# FPGA_I2C.net
KiCad netlist of a schematic drawn in Altium Designer
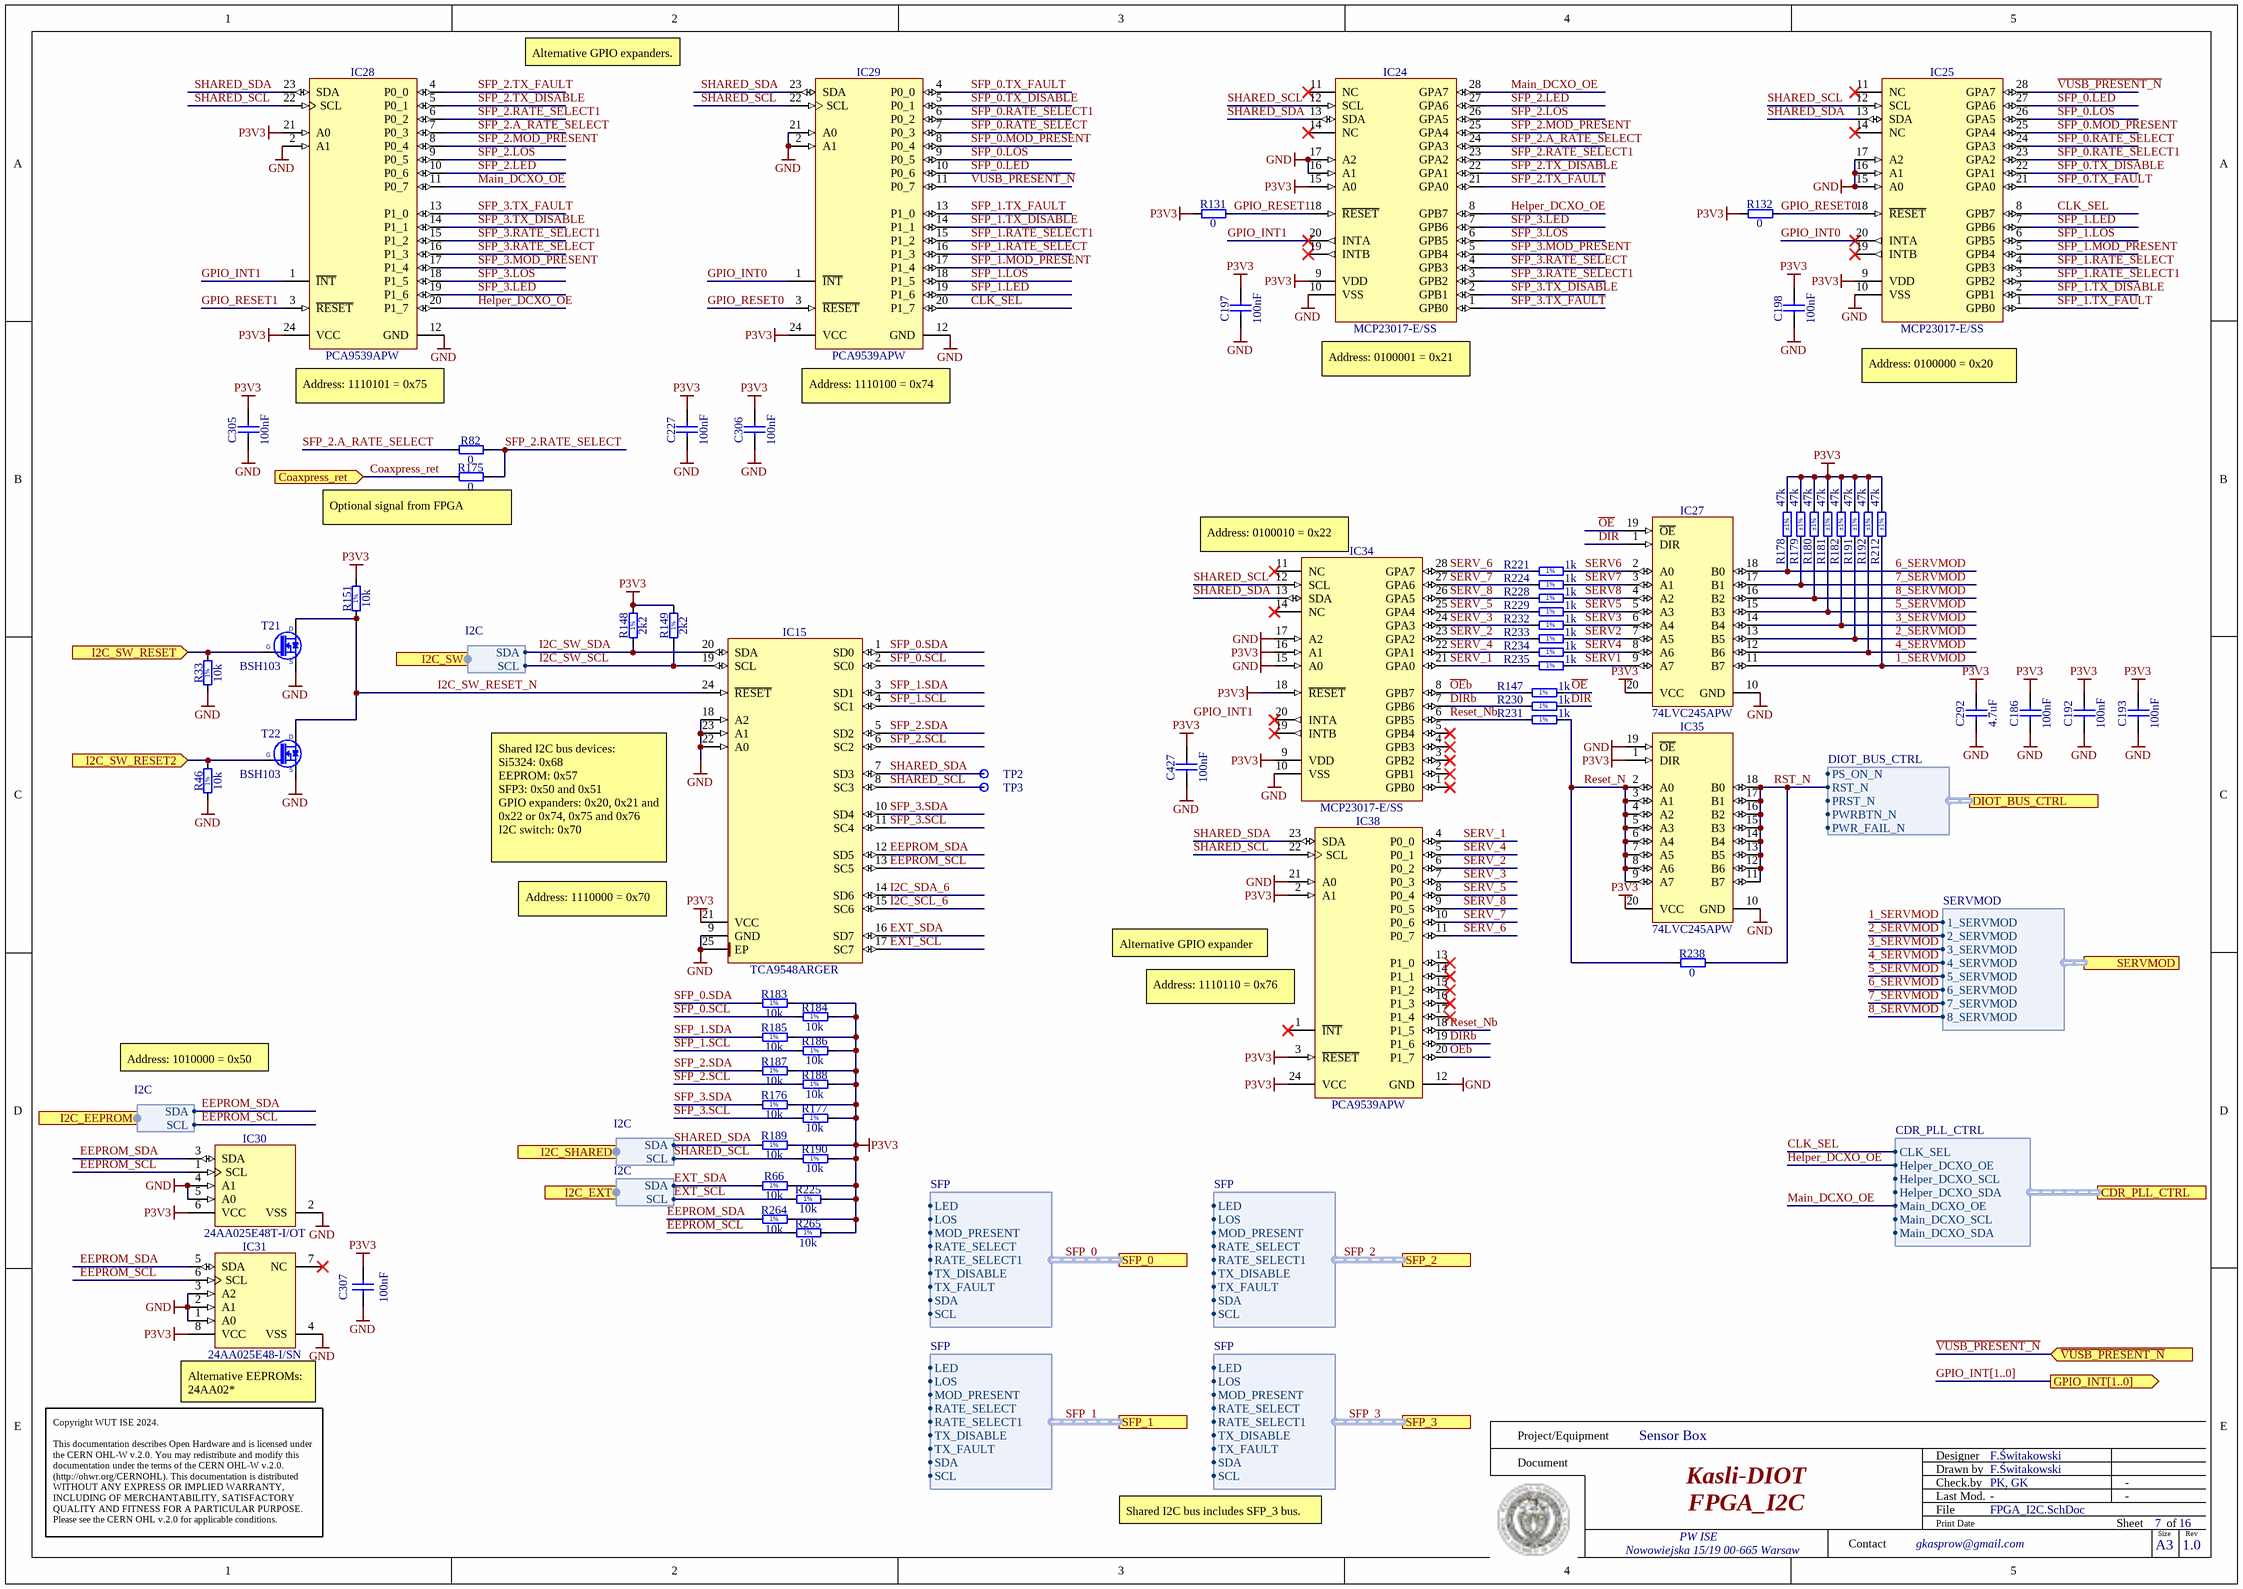
[diagram p0: FPGA_I2C.SchDoc]

(export (version "E")
  (design (tool "Eeschema 10.0.6"))
  (components
    (comp (ref "C186")
      (value "100nF")
      (footprint "CAPC1005X55N")
      (description "Non-polarised capacitor")
      (fields (field (name "PART NUMBER") "CC0402_100NF_16V_10%_X7R") (field (name "VOLTAGE") "16V"))
      (libsource (lib "Capacitors") (part "Capacitor - non polarized"))
    )
    (comp (ref "C192")
      (value "100nF")
      (footprint "CAPC1005X55N")
      (description "Non-polarised capacitor")
      (fields (field (name "PART NUMBER") "CC0402_100NF_16V_10%_X7R") (field (name "VOLTAGE") "16V"))
      (libsource (lib "Capacitors") (part "Capacitor - non polarized"))
    )
    (comp (ref "C193")
      (value "100nF")
      (footprint "CAPC1005X55N")
      (description "Non-polarised capacitor")
      (fields (field (name "PART NUMBER") "CC0402_100NF_16V_10%_X7R") (field (name "VOLTAGE") "16V"))
      (libsource (lib "Capacitors") (part "Capacitor - non polarized"))
    )
    (comp (ref "C197")
      (value "100nF")
      (footprint "CAPC1005X55N")
      (description "Non-polarised capacitor")
      (fields (field (name "PART NUMBER") "CC0402_100NF_16V_10%_X7R") (field (name "VOLTAGE") "16V"))
      (libsource (lib "Capacitors") (part "Capacitor - non polarized"))
    )
    (comp (ref "C198")
      (value "100nF")
      (footprint "CAPC1005X55N")
      (description "Non-polarised capacitor")
      (fields (field (name "PART NUMBER") "CC0402_100NF_16V_10%_X7R") (field (name "VOLTAGE") "16V"))
      (libsource (lib "Capacitors") (part "Capacitor - non polarized"))
    )
    (comp (ref "C227")
      (value "100nF")
      (footprint "CAPC1005X55N")
      (description "Non-polarised capacitor")
      (fields (field (name "PART NUMBER") "CC0402_100NF_16V_10%_X7R") (field (name "VOLTAGE") "16V"))
      (libsource (lib "Capacitors") (part "Capacitor - non polarized"))
    )
    (comp (ref "C292")
      (value "4.7uF")
      (footprint "CAPC1005X55N")
      (description "Non-polarised capacitor")
      (fields (field (name "PART NUMBER") "CC0402_4.7UF_6.3V_20%_X5R") (field (name "VOLTAGE") "6.3V"))
      (libsource (lib "Capacitors") (part "Capacitor - non polarized"))
    )
    (comp (ref "C305")
      (value "100nF")
      (footprint "CAPC1005X55N")
      (description "Non-polarised capacitor")
      (fields (field (name "PART NUMBER") "CC0402_100NF_16V_10%_X7R") (field (name "VOLTAGE") "16V"))
      (libsource (lib "Capacitors") (part "Capacitor - non polarized"))
    )
    (comp (ref "C306")
      (value "100nF")
      (footprint "CAPC1005X55N")
      (description "Non-polarised capacitor")
      (fields (field (name "PART NUMBER") "CC0402_100NF_16V_10%_X7R") (field (name "VOLTAGE") "16V"))
      (libsource (lib "Capacitors") (part "Capacitor - non polarized"))
    )
    (comp (ref "C307")
      (value "100nF")
      (footprint "CAPC1005X55N")
      (description "Non-polarised capacitor")
      (fields (field (name "PART NUMBER") "CC0402_100NF_16V_10%_X5R") (field (name "VOLTAGE") "16V"))
      (libsource (lib "Capacitors") (part "Capacitor - non polarized"))
    )
    (comp (ref "C427")
      (value "100nF")
      (footprint "CAPC1005X55N")
      (description "Non-polarised capacitor")
      (fields (field (name "PART NUMBER") "CC0402_100NF_16V_10%_X7R") (field (name "VOLTAGE") "16V"))
      (libsource (lib "Capacitors") (part "Capacitor - non polarized"))
    )
    (comp (ref "IC15")
      (value "TCA9548ARGER")
      (footprint "QFN50P400X400X100-25N-S220")
      (description "Low Voltage 8-Channel I2C Switch With Reset")
      (fields (field (name "MANUFACTURER") "TEXAS INSTRUMENTS"))
      (libsource (lib "ICs And Semiconductors") (part "TCA9548ARGER"))
    )
    (comp (ref "IC24")
      (value "MCP23017-E/SS")
      (footprint "SOP65P780X200-28N")
      (description "16-bit I/O Port Expander With Serial Interface")
      (fields (field (name "MANUFACTURER") "MICROCHIP TECHNOLOGY"))
      (libsource (lib "ICs And Semiconductors") (part "MCP23017-E/SS"))
    )
    (comp (ref "IC25")
      (value "MCP23017-E/SS")
      (footprint "SOP65P780X200-28N")
      (description "16-bit I/O Port Expander With Serial Interface")
      (fields (field (name "MANUFACTURER") "MICROCHIP TECHNOLOGY"))
      (libsource (lib "ICs And Semiconductors") (part "MCP23017-E/SS"))
    )
    (comp (ref "IC27")
      (value "74LVC245APW")
      (footprint "SOP65P640X110-20N")
      (description "Octal Bi-Directional Transceiver with 3-State Inputs/Outputs")
      (fields (field (name "MANUFACTURER") "NXP SEMICONDUCTORS"))
      (libsource (lib "ICs And Semiconductors") (part "74245"))
    )
    (comp (ref "IC28")
      (value "PCA9539APW")
      (footprint "SOP65P640X110-24N")
      (description "Low-Voltage 16-Bit I2C-Bus I/O Port with Interrupt and Reset")
      (fields (field (name "MANUFACTURER") "NXP SEMICONDUCTORS"))
      (libsource (lib "ICs And Semiconductors") (part "PCA9539APW"))
    )
    (comp (ref "IC29")
      (value "PCA9539APW")
      (footprint "SOP65P640X110-24N")
      (description "Low-Voltage 16-Bit I2C-Bus I/O Port with Interrupt and Reset")
      (fields (field (name "MANUFACTURER") "NXP SEMICONDUCTORS"))
      (libsource (lib "ICs And Semiconductors") (part "PCA9539APW"))
    )
    (comp (ref "IC30")
      (value "24AA025E48T-I/OT")
      (footprint "SOT95P280X145-6N")
      (description "1.7V-5.5V, 2K I2C Serial EEPROM With EUI-48 Node Identity")
      (fields (field (name "MANUFACTURER") "MICROCHIP TECHNOLOGY"))
      (libsource (lib "ICs And Semiconductors") (part "24AA025E48T-I/OT"))
    )
    (comp (ref "IC31")
      (value "24AA025E48-I/SN")
      (footprint "SOIC127P600X175-8N")
      (description "1.7V-5.5V, 2K I2C™ Serial EEPROMs with EUI-48™ Node Identity")
      (fields (field (name "MANUFACTURER") "MICROCHIP TECHNOLOGY"))
      (libsource (lib "ICs And Semiconductors") (part "24AA025E48-I/SN"))
    )
    (comp (ref "IC34")
      (value "MCP23017-E/SS")
      (footprint "SOP65P780X200-28N")
      (description "16-bit I/O Port Expander With Serial Interface")
      (fields (field (name "MANUFACTURER") "MICROCHIP TECHNOLOGY"))
      (libsource (lib "ICs And Semiconductors") (part "MCP23017-E/SS"))
    )
    (comp (ref "IC35")
      (value "74LVC245APW")
      (footprint "SOP65P640X110-20N")
      (description "Octal Bi-Directional Transceiver with 3-State Inputs/Outputs")
      (fields (field (name "MANUFACTURER") "NXP SEMICONDUCTORS"))
      (libsource (lib "ICs And Semiconductors") (part "74245"))
    )
    (comp (ref "IC38")
      (value "PCA9539APW")
      (footprint "SOP65P640X110-24N")
      (description "Low-Voltage 16-Bit I2C-Bus I/O Port with Interrupt and Reset")
      (fields (field (name "MANUFACTURER") "NXP SEMICONDUCTORS"))
      (libsource (lib "ICs And Semiconductors") (part "PCA9539APW"))
    )
    (comp (ref "R33")
      (value "10k")
      (footprint "RESC1005X40N")
      (description "Resistor - 1%")
      (fields (field (name "PART NUMBER") "R0402_10K_1%_0.0625W_100PPM") (field (name "POWER") "0.0625W"))
      (libsource (lib "Resistors") (part "Resistor - 1%"))
    )
    (comp (ref "R46")
      (value "10k")
      (footprint "RESC1005X40N")
      (description "Resistor - 1%")
      (fields (field (name "PART NUMBER") "R0402_10K_1%_0.0625W_100PPM") (field (name "POWER") "0.0625W"))
      (libsource (lib "Resistors") (part "Resistor - 1%"))
    )
    (comp (ref "R66")
      (value "10k")
      (footprint "RESC1005X40N")
      (description "Resistor - 1%")
      (fields (field (name "PART NUMBER") "R0402_10K_1%_0.0625W_100PPM") (field (name "POWER") "0.0625W"))
      (libsource (lib "Resistors") (part "Resistor - 1%"))
    )
    (comp (ref "R82")
      (value "0")
      (footprint "RESC1005X40N")
      (description "Resistor")
      (fields (field (name "PART NUMBER") "R0402_0R_JUMPER") (field (name "MANUFACTURER") "GENERIC"))
      (libsource (lib "Resistors") (part "Resistor"))
    )
    (comp (ref "R131")
      (value "0")
      (footprint "RESC1005X40N")
      (description "Resistor")
      (fields (field (name "PART NUMBER") "R0402_0R_JUMPER") (field (name "MANUFACTURER") "GENERIC"))
      (libsource (lib "Resistors") (part "Resistor"))
    )
    (comp (ref "R132")
      (value "0")
      (footprint "RESC1005X40N")
      (description "Resistor")
      (fields (field (name "PART NUMBER") "R0402_0R_JUMPER") (field (name "MANUFACTURER") "GENERIC"))
      (libsource (lib "Resistors") (part "Resistor"))
    )
    (comp (ref "R147")
      (value "1k")
      (footprint "RESC1005X40N")
      (description "Resistor - 1%")
      (fields (field (name "PART NUMBER") "R0402_1K_1%_0.0625W_100PPM") (field (name "POWER") "0.0625W"))
      (libsource (lib "Resistors") (part "Resistor - 1%"))
    )
    (comp (ref "R148")
      (value "2k2")
      (footprint "RESC1005X40N")
      (description "Resistor - 1%")
      (fields (field (name "PART NUMBER") "R0402_2K2_1%_0.0625W_100PPM") (field (name "POWER") "0.0625W"))
      (libsource (lib "Resistors") (part "Resistor - 1%"))
    )
    (comp (ref "R149")
      (value "2k2")
      (footprint "RESC1005X40N")
      (description "Resistor - 1%")
      (fields (field (name "PART NUMBER") "R0402_2K2_1%_0.0625W_100PPM") (field (name "POWER") "0.0625W"))
      (libsource (lib "Resistors") (part "Resistor - 1%"))
    )
    (comp (ref "R151")
      (value "10k")
      (footprint "RESC1005X40N")
      (description "Resistor - 1%")
      (fields (field (name "PART NUMBER") "R0402_10K_1%_0.0625W_100PPM") (field (name "POWER") "0.0625W"))
      (libsource (lib "Resistors") (part "Resistor - 1%"))
    )
    (comp (ref "R175")
      (value "0")
      (footprint "RESC1005X40N")
      (description "Resistor")
      (fields (field (name "PART NUMBER") "R0402_0R_JUMPER") (field (name "MANUFACTURER") "GENERIC"))
      (libsource (lib "Resistors") (part "Resistor"))
    )
    (comp (ref "R176")
      (value "10k")
      (footprint "RESC1005X40N")
      (description "Resistor - 1%")
      (fields (field (name "PART NUMBER") "R0402_10K_1%_0.0625W_100PPM") (field (name "POWER") "0.0625W"))
      (libsource (lib "Resistors") (part "Resistor - 1%"))
    )
    (comp (ref "R177")
      (value "10k")
      (footprint "RESC1005X40N")
      (description "Resistor - 1%")
      (fields (field (name "PART NUMBER") "R0402_10K_1%_0.0625W_100PPM") (field (name "POWER") "0.0625W"))
      (libsource (lib "Resistors") (part "Resistor - 1%"))
    )
    (comp (ref "R178")
      (value "47k")
      (footprint "RESC1005X40N")
      (description "Resistor - 1%")
      (fields
        (field (name "TOLERANCE") "±1%")
        (field (name "PART NUMBER") "R0402_47K_1%_0.0625W_100PPM")
        (field (name "POWER") "0.0625W")
      )
      (libsource (lib "Resistors") (part "Resistor - 1%"))
    )
    (comp (ref "R179")
      (value "47k")
      (footprint "RESC1005X40N")
      (description "Resistor - 1%")
      (fields
        (field (name "TOLERANCE") "±1%")
        (field (name "PART NUMBER") "R0402_47K_1%_0.0625W_100PPM")
        (field (name "POWER") "0.0625W")
      )
      (libsource (lib "Resistors") (part "Resistor - 1%"))
    )
    (comp (ref "R180")
      (value "47k")
      (footprint "RESC1005X40N")
      (description "Resistor - 1%")
      (fields
        (field (name "TOLERANCE") "±1%")
        (field (name "PART NUMBER") "R0402_47K_1%_0.0625W_100PPM")
        (field (name "POWER") "0.0625W")
      )
      (libsource (lib "Resistors") (part "Resistor - 1%"))
    )
    (comp (ref "R181")
      (value "47k")
      (footprint "RESC1005X40N")
      (description "Resistor - 1%")
      (fields
        (field (name "TOLERANCE") "±1%")
        (field (name "PART NUMBER") "R0402_47K_1%_0.0625W_100PPM")
        (field (name "POWER") "0.0625W")
      )
      (libsource (lib "Resistors") (part "Resistor - 1%"))
    )
    (comp (ref "R182")
      (value "47k")
      (footprint "RESC1005X40N")
      (description "Resistor - 1%")
      (fields
        (field (name "TOLERANCE") "±1%")
        (field (name "PART NUMBER") "R0402_47K_1%_0.0625W_100PPM")
        (field (name "POWER") "0.0625W")
      )
      (libsource (lib "Resistors") (part "Resistor - 1%"))
    )
    (comp (ref "R183")
      (value "10k")
      (footprint "RESC1005X40N")
      (description "Resistor - 1%")
      (fields (field (name "PART NUMBER") "R0402_10K_1%_0.0625W_100PPM") (field (name "POWER") "0.0625W"))
      (libsource (lib "Resistors") (part "Resistor - 1%"))
    )
    (comp (ref "R184")
      (value "10k")
      (footprint "RESC1005X40N")
      (description "Resistor - 1%")
      (fields (field (name "PART NUMBER") "R0402_10K_1%_0.0625W_100PPM") (field (name "POWER") "0.0625W"))
      (libsource (lib "Resistors") (part "Resistor - 1%"))
    )
    (comp (ref "R185")
      (value "10k")
      (footprint "RESC1005X40N")
      (description "Resistor - 1%")
      (fields (field (name "PART NUMBER") "R0402_10K_1%_0.0625W_100PPM") (field (name "POWER") "0.0625W"))
      (libsource (lib "Resistors") (part "Resistor - 1%"))
    )
    (comp (ref "R186")
      (value "10k")
      (footprint "RESC1005X40N")
      (description "Resistor - 1%")
      (fields (field (name "PART NUMBER") "R0402_10K_1%_0.0625W_100PPM") (field (name "POWER") "0.0625W"))
      (libsource (lib "Resistors") (part "Resistor - 1%"))
    )
    (comp (ref "R187")
      (value "10k")
      (footprint "RESC1005X40N")
      (description "Resistor - 1%")
      (fields (field (name "PART NUMBER") "R0402_10K_1%_0.0625W_100PPM") (field (name "POWER") "0.0625W"))
      (libsource (lib "Resistors") (part "Resistor - 1%"))
    )
    (comp (ref "R188")
      (value "10k")
      (footprint "RESC1005X40N")
      (description "Resistor - 1%")
      (fields (field (name "PART NUMBER") "R0402_10K_1%_0.0625W_100PPM") (field (name "POWER") "0.0625W"))
      (libsource (lib "Resistors") (part "Resistor - 1%"))
    )
    (comp (ref "R189")
      (value "10k")
      (footprint "RESC1005X40N")
      (description "Resistor - 1%")
      (fields (field (name "PART NUMBER") "R0402_10K_1%_0.0625W_100PPM") (field (name "POWER") "0.0625W"))
      (libsource (lib "Resistors") (part "Resistor - 1%"))
    )
    (comp (ref "R190")
      (value "10k")
      (footprint "RESC1005X40N")
      (description "Resistor - 1%")
      (fields (field (name "PART NUMBER") "R0402_10K_1%_0.0625W_100PPM") (field (name "POWER") "0.0625W"))
      (libsource (lib "Resistors") (part "Resistor - 1%"))
    )
    (comp (ref "R191")
      (value "47k")
      (footprint "RESC1005X40N")
      (description "Resistor - 1%")
      (fields
        (field (name "TOLERANCE") "±1%")
        (field (name "PART NUMBER") "R0402_47K_1%_0.0625W_100PPM")
        (field (name "POWER") "0.0625W")
      )
      (libsource (lib "Resistors") (part "Resistor - 1%"))
    )
    (comp (ref "R192")
      (value "47k")
      (footprint "RESC1005X40N")
      (description "Resistor - 1%")
      (fields
        (field (name "TOLERANCE") "±1%")
        (field (name "PART NUMBER") "R0402_47K_1%_0.0625W_100PPM")
        (field (name "POWER") "0.0625W")
      )
      (libsource (lib "Resistors") (part "Resistor - 1%"))
    )
    (comp (ref "R212")
      (value "47k")
      (footprint "RESC1005X40N")
      (description "Resistor - 1%")
      (fields
        (field (name "TOLERANCE") "±1%")
        (field (name "PART NUMBER") "R0402_47K_1%_0.0625W_100PPM")
        (field (name "POWER") "0.0625W")
      )
      (libsource (lib "Resistors") (part "Resistor - 1%"))
    )
    (comp (ref "R221")
      (value "1k")
      (footprint "RESC1005X40N")
      (description "Resistor - 1%")
      (fields (field (name "PART NUMBER") "R0402_1K_1%_0.0625W_100PPM") (field (name "POWER") "0.0625W"))
      (libsource (lib "Resistors") (part "Resistor - 1%"))
    )
    (comp (ref "R224")
      (value "1k")
      (footprint "RESC1005X40N")
      (description "Resistor - 1%")
      (fields (field (name "PART NUMBER") "R0402_1K_1%_0.0625W_100PPM") (field (name "POWER") "0.0625W"))
      (libsource (lib "Resistors") (part "Resistor - 1%"))
    )
    (comp (ref "R225")
      (value "10k")
      (footprint "RESC1005X40N")
      (description "Resistor - 1%")
      (fields (field (name "PART NUMBER") "R0402_10K_1%_0.0625W_100PPM") (field (name "POWER") "0.0625W"))
      (libsource (lib "Resistors") (part "Resistor - 1%"))
    )
    (comp (ref "R228")
      (value "1k")
      (footprint "RESC1005X40N")
      (description "Resistor - 1%")
      (fields (field (name "PART NUMBER") "R0402_1K_1%_0.0625W_100PPM") (field (name "POWER") "0.0625W"))
      (libsource (lib "Resistors") (part "Resistor - 1%"))
    )
    (comp (ref "R229")
      (value "1k")
      (footprint "RESC1005X40N")
      (description "Resistor - 1%")
      (fields (field (name "PART NUMBER") "R0402_1K_1%_0.0625W_100PPM") (field (name "POWER") "0.0625W"))
      (libsource (lib "Resistors") (part "Resistor - 1%"))
    )
    (comp (ref "R230")
      (value "1k")
      (footprint "RESC1005X40N")
      (description "Resistor - 1%")
      (fields (field (name "PART NUMBER") "R0402_1K_1%_0.0625W_100PPM") (field (name "POWER") "0.0625W"))
      (libsource (lib "Resistors") (part "Resistor - 1%"))
    )
    (comp (ref "R231")
      (value "1k")
      (footprint "RESC1005X40N")
      (description "Resistor - 1%")
      (fields (field (name "PART NUMBER") "R0402_1K_1%_0.0625W_100PPM") (field (name "POWER") "0.0625W"))
      (libsource (lib "Resistors") (part "Resistor - 1%"))
    )
    (comp (ref "R232")
      (value "1k")
      (footprint "RESC1005X40N")
      (description "Resistor - 1%")
      (fields (field (name "PART NUMBER") "R0402_1K_1%_0.0625W_100PPM") (field (name "POWER") "0.0625W"))
      (libsource (lib "Resistors") (part "Resistor - 1%"))
    )
    (comp (ref "R233")
      (value "1k")
      (footprint "RESC1005X40N")
      (description "Resistor - 1%")
      (fields (field (name "PART NUMBER") "R0402_1K_1%_0.0625W_100PPM") (field (name "POWER") "0.0625W"))
      (libsource (lib "Resistors") (part "Resistor - 1%"))
    )
    (comp (ref "R234")
      (value "1k")
      (footprint "RESC1005X40N")
      (description "Resistor - 1%")
      (fields (field (name "PART NUMBER") "R0402_1K_1%_0.0625W_100PPM") (field (name "POWER") "0.0625W"))
      (libsource (lib "Resistors") (part "Resistor - 1%"))
    )
    (comp (ref "R235")
      (value "1k")
      (footprint "RESC1005X40N")
      (description "Resistor - 1%")
      (fields (field (name "PART NUMBER") "R0402_1K_1%_0.0625W_100PPM") (field (name "POWER") "0.0625W"))
      (libsource (lib "Resistors") (part "Resistor - 1%"))
    )
    (comp (ref "R238")
      (value "0")
      (footprint "RESC1005X40N")
      (description "Resistor")
      (fields (field (name "PART NUMBER") "R0402_0R_JUMPER") (field (name "MANUFACTURER") "GENERIC"))
      (libsource (lib "Resistors") (part "Resistor"))
    )
    (comp (ref "R264")
      (value "10k")
      (footprint "RESC1005X40N")
      (description "Resistor - 1%")
      (fields (field (name "PART NUMBER") "R0402_10K_1%_0.0625W_100PPM") (field (name "POWER") "0.0625W"))
      (libsource (lib "Resistors") (part "Resistor - 1%"))
    )
    (comp (ref "R265")
      (value "10k")
      (footprint "RESC1005X40N")
      (description "Resistor - 1%")
      (fields (field (name "PART NUMBER") "R0402_10K_1%_0.0625W_100PPM") (field (name "POWER") "0.0625W"))
      (libsource (lib "Resistors") (part "Resistor - 1%"))
    )
    (comp (ref "T21")
      (value "BSH103")
      (footprint "SOT95P230X110-3N")
      (description "N-CHANNEL MOSFET WITH DIODE")
      (fields (field (name "MANUFACTURER") "NEXPERIA"))
      (libsource (lib "ICs And Semiconductors") (part "N-MOSFET-D 1G 2S 3D"))
    )
    (comp (ref "T22")
      (value "BSH103")
      (footprint "SOT95P230X110-3N")
      (description "N-CHANNEL MOSFET WITH DIODE")
      (fields (field (name "MANUFACTURER") "NEXPERIA"))
      (libsource (lib "ICs And Semiconductors") (part "N-MOSFET-D 1G 2S 3D"))
    )
    (comp (ref "TP2")
      (value "Test Point")
      (footprint "TPS127")
      (fields (field (name "PART NUMBER") "SMD_PAD_1.27X1.27MM"))
      (libsource (lib "Eletro-mechanical") (part "Test Point"))
    )
    (comp (ref "TP3")
      (value "Test Point")
      (footprint "TPS127")
      (fields (field (name "PART NUMBER") "SMD_PAD_1.27X1.27MM"))
      (libsource (lib "Eletro-mechanical") (part "Test Point"))
    )
  )
  (nets
    (net (code "9") (name "/1_SERVMOD") (class "Default")
      (node (ref "IC27") (pin "11") (pinfunction "B7_11") (pintype "bidirectional"))
      (node (ref "R212") (pin "1") (pinfunction "1_1") (pintype "passive"))
    )
    (net (code "10") (name "/2_SERVMOD") (class "Default")
      (node (ref "IC27") (pin "13") (pinfunction "B5_13") (pintype "bidirectional"))
      (node (ref "R191") (pin "1") (pinfunction "1_1") (pintype "passive"))
    )
    (net (code "11") (name "/3_SERVMOD") (class "Default")
      (node (ref "IC27") (pin "14") (pinfunction "B4_14") (pintype "bidirectional"))
      (node (ref "R182") (pin "1") (pinfunction "1_1") (pintype "passive"))
    )
    (net (code "12") (name "/4_SERVMOD") (class "Default")
      (node (ref "IC27") (pin "12") (pinfunction "B6_12") (pintype "bidirectional"))
      (node (ref "R192") (pin "1") (pinfunction "1_1") (pintype "passive"))
    )
    (net (code "13") (name "/5_SERVMOD") (class "Default")
      (node (ref "IC27") (pin "15") (pinfunction "B3_15") (pintype "bidirectional"))
      (node (ref "R181") (pin "1") (pinfunction "1_1") (pintype "passive"))
    )
    (net (code "14") (name "/6_SERVMOD") (class "Default")
      (node (ref "IC27") (pin "18") (pinfunction "B0_18") (pintype "bidirectional"))
      (node (ref "R178") (pin "1") (pinfunction "1_1") (pintype "passive"))
    )
    (net (code "15") (name "/7_SERVMOD") (class "Default")
      (node (ref "IC27") (pin "17") (pinfunction "B1_17") (pintype "bidirectional"))
      (node (ref "R179") (pin "1") (pinfunction "1_1") (pintype "passive"))
    )
    (net (code "16") (name "/8_SERVMOD") (class "Default")
      (node (ref "IC27") (pin "16") (pinfunction "B2_16") (pintype "bidirectional"))
      (node (ref "R180") (pin "1") (pinfunction "1_1") (pintype "passive"))
    )
    (net (code "17") (name "/CLK_SEL") (class "Default")
      (node (ref "IC25") (pin "8") (pinfunction "GPB7_8") (pintype "bidirectional"))
      (node (ref "IC29") (pin "20") (pinfunction "P1_7_20") (pintype "bidirectional"))
    )
    (net (code "18") (name "/Coaxpress_ret") (class "Default")
      (node (ref "R175") (pin "1") (pinfunction "1_1") (pintype "passive"))
    )
    (net (code "19") (name "/DIR") (class "Default")
      (node (ref "IC27") (pin "1") (pinfunction "DIR_1") (pintype "input"))
      (node (ref "R230") (pin "2") (pinfunction "2_2") (pintype "passive"))
    )
    (net (code "20") (name "/DIRb") (class "Default")
      (node (ref "IC34") (pin "7") (pinfunction "GPB6_7") (pintype "bidirectional"))
      (node (ref "IC38") (pin "19") (pinfunction "P1_6_19") (pintype "bidirectional"))
      (node (ref "R230") (pin "1") (pinfunction "1_1") (pintype "passive"))
    )
    (net (code "21") (name "/EEPROM_SCL") (class "Default")
      (node (ref "IC15") (pin "13") (pinfunction "SC5_13") (pintype "bidirectional"))
      (node (ref "IC30") (pin "1") (pinfunction "SCL_1") (pintype "input"))
      (node (ref "IC31") (pin "6") (pinfunction "SCL_6") (pintype "input"))
      (node (ref "R265") (pin "1") (pinfunction "1_1") (pintype "passive"))
    )
    (net (code "22") (name "/EEPROM_SDA") (class "Default")
      (node (ref "IC15") (pin "12") (pinfunction "SD5_12") (pintype "bidirectional"))
      (node (ref "IC30") (pin "3") (pinfunction "SDA_3") (pintype "bidirectional"))
      (node (ref "IC31") (pin "5") (pinfunction "SDA_5") (pintype "bidirectional"))
      (node (ref "R264") (pin "1") (pinfunction "1_1") (pintype "passive"))
    )
    (net (code "23") (name "/EXT_SCL") (class "Default")
      (node (ref "IC15") (pin "17") (pinfunction "SC7_17") (pintype "bidirectional"))
      (node (ref "R225") (pin "1") (pinfunction "1_1") (pintype "passive"))
    )
    (net (code "24") (name "/EXT_SDA") (class "Default")
      (node (ref "IC15") (pin "16") (pinfunction "SD7_16") (pintype "bidirectional"))
      (node (ref "R66") (pin "1") (pinfunction "1_1") (pintype "passive"))
    )
    (net (code "25") (name "/GPIO_INT0") (class "Default")
      (node (ref "IC25") (pin "20") (pinfunction "INTA_20") (pintype "output"))
      (node (ref "IC29") (pin "1") (pinfunction "~{INT}_1") (pintype "open_collector"))
    )
    (net (code "26") (name "/GPIO_INT1") (class "Default")
      (node (ref "IC24") (pin "20") (pinfunction "INTA_20") (pintype "output"))
      (node (ref "IC28") (pin "1") (pinfunction "~{INT}_1") (pintype "open_collector"))
    )
    (net (code "28") (name "/GPIO_RESET0") (class "Default")
      (node (ref "IC25") (pin "18") (pinfunction "~{RESET}_18") (pintype "input"))
      (node (ref "IC29") (pin "3") (pinfunction "~{RESET}_3") (pintype "input"))
      (node (ref "R132") (pin "2") (pinfunction "2_2") (pintype "passive"))
    )
    (net (code "29") (name "/GPIO_RESET1") (class "Default")
      (node (ref "IC24") (pin "18") (pinfunction "~{RESET}_18") (pintype "input"))
      (node (ref "IC28") (pin "3") (pinfunction "~{RESET}_3") (pintype "input"))
      (node (ref "R131") (pin "2") (pinfunction "2_2") (pintype "passive"))
    )
    (net (code "30") (name "/Helper_DCXO_OE") (class "Default")
      (node (ref "IC24") (pin "8") (pinfunction "GPB7_8") (pintype "bidirectional"))
      (node (ref "IC28") (pin "20") (pinfunction "P1_7_20") (pintype "bidirectional"))
    )
    (net (code "31") (name "/I2C_SCL_6") (class "Default")
      (node (ref "IC15") (pin "15") (pinfunction "SC6_15") (pintype "bidirectional"))
    )
    (net (code "32") (name "/I2C_SDA_6") (class "Default")
      (node (ref "IC15") (pin "14") (pinfunction "SD6_14") (pintype "bidirectional"))
    )
    (net (code "33") (name "/I2C_SW_RESET") (class "Default")
      (node (ref "R33") (pin "2") (pinfunction "2_2") (pintype "passive"))
      (node (ref "T21") (pin "1") (pinfunction "G_1") (pintype "passive"))
    )
    (net (code "34") (name "/I2C_SW_RESET2") (class "Default")
      (node (ref "R46") (pin "2") (pinfunction "2_2") (pintype "passive"))
      (node (ref "T22") (pin "1") (pinfunction "G_1") (pintype "passive"))
    )
    (net (code "35") (name "/I2C_SW_RESET_N") (class "Default")
      (node (ref "IC15") (pin "24") (pinfunction "~{RESET}_24") (pintype "input"))
      (node (ref "R151") (pin "1") (pinfunction "1_1") (pintype "passive"))
      (node (ref "T21") (pin "3") (pinfunction "D_3") (pintype "passive"))
      (node (ref "T22") (pin "3") (pinfunction "D_3") (pintype "passive"))
    )
    (net (code "36") (name "/I2C_SW_SCL") (class "Default")
      (node (ref "IC15") (pin "19") (pinfunction "SCL_19") (pintype "bidirectional"))
      (node (ref "R149") (pin "1") (pinfunction "1_1") (pintype "passive"))
    )
    (net (code "37") (name "/I2C_SW_SDA") (class "Default")
      (node (ref "IC15") (pin "20") (pinfunction "SDA_20") (pintype "bidirectional"))
      (node (ref "R148") (pin "1") (pinfunction "1_1") (pintype "passive"))
    )
    (net (code "38") (name "/Main_DCXO_OE") (class "Default")
      (node (ref "IC24") (pin "28") (pinfunction "GPA7_28") (pintype "bidirectional"))
      (node (ref "IC28") (pin "11") (pinfunction "P0_7_11") (pintype "bidirectional"))
    )
    (net (code "39") (name "/RST_N") (class "Default")
      (node (ref "IC35") (pin "11") (pinfunction "B7_11") (pintype "bidirectional"))
      (node (ref "IC35") (pin "12") (pinfunction "B6_12") (pintype "bidirectional"))
      (node (ref "IC35") (pin "13") (pinfunction "B5_13") (pintype "bidirectional"))
      (node (ref "IC35") (pin "14") (pinfunction "B4_14") (pintype "bidirectional"))
      (node (ref "IC35") (pin "15") (pinfunction "B3_15") (pintype "bidirectional"))
      (node (ref "IC35") (pin "16") (pinfunction "B2_16") (pintype "bidirectional"))
      (node (ref "IC35") (pin "17") (pinfunction "B1_17") (pintype "bidirectional"))
      (node (ref "IC35") (pin "18") (pinfunction "B0_18") (pintype "bidirectional"))
      (node (ref "R238") (pin "2") (pinfunction "2_2") (pintype "passive"))
    )
    (net (code "40") (name "/Reset_N") (class "Default")
      (node (ref "IC35") (pin "2") (pinfunction "A0_2") (pintype "bidirectional"))
      (node (ref "IC35") (pin "3") (pinfunction "A1_3") (pintype "bidirectional"))
      (node (ref "IC35") (pin "4") (pinfunction "A2_4") (pintype "bidirectional"))
      (node (ref "IC35") (pin "5") (pinfunction "A3_5") (pintype "bidirectional"))
      (node (ref "IC35") (pin "6") (pinfunction "A4_6") (pintype "bidirectional"))
      (node (ref "IC35") (pin "7") (pinfunction "A5_7") (pintype "bidirectional"))
      (node (ref "IC35") (pin "8") (pinfunction "A6_8") (pintype "bidirectional"))
      (node (ref "IC35") (pin "9") (pinfunction "A7_9") (pintype "bidirectional"))
      (node (ref "R231") (pin "2") (pinfunction "2_2") (pintype "passive"))
      (node (ref "R238") (pin "1") (pinfunction "1_1") (pintype "passive"))
    )
    (net (code "41") (name "/Reset_Nb") (class "Default")
      (node (ref "IC34") (pin "6") (pinfunction "GPB5_6") (pintype "bidirectional"))
      (node (ref "IC38") (pin "18") (pinfunction "P1_5_18") (pintype "bidirectional"))
      (node (ref "R231") (pin "1") (pinfunction "1_1") (pintype "passive"))
    )
    (net (code "42") (name "/SERV1") (class "Default")
      (node (ref "IC27") (pin "9") (pinfunction "A7_9") (pintype "bidirectional"))
      (node (ref "R235") (pin "2") (pinfunction "2_2") (pintype "passive"))
    )
    (net (code "43") (name "/SERV2") (class "Default")
      (node (ref "IC27") (pin "7") (pinfunction "A5_7") (pintype "bidirectional"))
      (node (ref "R233") (pin "2") (pinfunction "2_2") (pintype "passive"))
    )
    (net (code "44") (name "/SERV3") (class "Default")
      (node (ref "IC27") (pin "6") (pinfunction "A4_6") (pintype "bidirectional"))
      (node (ref "R232") (pin "2") (pinfunction "2_2") (pintype "passive"))
    )
    (net (code "45") (name "/SERV4") (class "Default")
      (node (ref "IC27") (pin "8") (pinfunction "A6_8") (pintype "bidirectional"))
      (node (ref "R234") (pin "2") (pinfunction "2_2") (pintype "passive"))
    )
    (net (code "46") (name "/SERV5") (class "Default")
      (node (ref "IC27") (pin "5") (pinfunction "A3_5") (pintype "bidirectional"))
      (node (ref "R229") (pin "2") (pinfunction "2_2") (pintype "passive"))
    )
    (net (code "47") (name "/SERV6") (class "Default")
      (node (ref "IC27") (pin "2") (pinfunction "A0_2") (pintype "bidirectional"))
      (node (ref "R221") (pin "2") (pinfunction "2_2") (pintype "passive"))
    )
    (net (code "48") (name "/SERV7") (class "Default")
      (node (ref "IC27") (pin "3") (pinfunction "A1_3") (pintype "bidirectional"))
      (node (ref "R224") (pin "2") (pinfunction "2_2") (pintype "passive"))
    )
    (net (code "49") (name "/SERV8") (class "Default")
      (node (ref "IC27") (pin "4") (pinfunction "A2_4") (pintype "bidirectional"))
      (node (ref "R228") (pin "2") (pinfunction "2_2") (pintype "passive"))
    )
    (net (code "50") (name "/SERV_1") (class "Default")
      (node (ref "IC34") (pin "21") (pinfunction "GPA0_21") (pintype "bidirectional"))
      (node (ref "IC38") (pin "4") (pinfunction "P0_0_4") (pintype "bidirectional"))
      (node (ref "R235") (pin "1") (pinfunction "1_1") (pintype "passive"))
    )
    (net (code "51") (name "/SERV_2") (class "Default")
      (node (ref "IC34") (pin "23") (pinfunction "GPA2_23") (pintype "bidirectional"))
      (node (ref "IC38") (pin "6") (pinfunction "P0_2_6") (pintype "bidirectional"))
      (node (ref "R233") (pin "1") (pinfunction "1_1") (pintype "passive"))
    )
    (net (code "52") (name "/SERV_3") (class "Default")
      (node (ref "IC34") (pin "24") (pinfunction "GPA3_24") (pintype "bidirectional"))
      (node (ref "IC38") (pin "7") (pinfunction "P0_3_7") (pintype "bidirectional"))
      (node (ref "R232") (pin "1") (pinfunction "1_1") (pintype "passive"))
    )
    (net (code "53") (name "/SERV_4") (class "Default")
      (node (ref "IC34") (pin "22") (pinfunction "GPA1_22") (pintype "bidirectional"))
      (node (ref "IC38") (pin "5") (pinfunction "P0_1_5") (pintype "bidirectional"))
      (node (ref "R234") (pin "1") (pinfunction "1_1") (pintype "passive"))
    )
    (net (code "54") (name "/SERV_5") (class "Default")
      (node (ref "IC34") (pin "25") (pinfunction "GPA4_25") (pintype "bidirectional"))
      (node (ref "IC38") (pin "8") (pinfunction "P0_4_8") (pintype "bidirectional"))
      (node (ref "R229") (pin "1") (pinfunction "1_1") (pintype "passive"))
    )
    (net (code "55") (name "/SERV_6") (class "Default")
      (node (ref "IC34") (pin "28") (pinfunction "GPA7_28") (pintype "bidirectional"))
      (node (ref "IC38") (pin "11") (pinfunction "P0_7_11") (pintype "bidirectional"))
      (node (ref "R221") (pin "1") (pinfunction "1_1") (pintype "passive"))
    )
    (net (code "56") (name "/SERV_7") (class "Default")
      (node (ref "IC34") (pin "27") (pinfunction "GPA6_27") (pintype "bidirectional"))
      (node (ref "IC38") (pin "10") (pinfunction "P0_6_10") (pintype "bidirectional"))
      (node (ref "R224") (pin "1") (pinfunction "1_1") (pintype "passive"))
    )
    (net (code "57") (name "/SERV_8") (class "Default")
      (node (ref "IC34") (pin "26") (pinfunction "GPA5_26") (pintype "bidirectional"))
      (node (ref "IC38") (pin "9") (pinfunction "P0_5_9") (pintype "bidirectional"))
      (node (ref "R228") (pin "1") (pinfunction "1_1") (pintype "passive"))
    )
    (net (code "58") (name "/SFP_0.LED") (class "Default")
      (node (ref "IC25") (pin "27") (pinfunction "GPA6_27") (pintype "bidirectional"))
      (node (ref "IC29") (pin "10") (pinfunction "P0_6_10") (pintype "bidirectional"))
    )
    (net (code "59") (name "/SFP_0.LOS") (class "Default")
      (node (ref "IC25") (pin "26") (pinfunction "GPA5_26") (pintype "bidirectional"))
      (node (ref "IC29") (pin "9") (pinfunction "P0_5_9") (pintype "bidirectional"))
    )
    (net (code "60") (name "/SFP_0.MOD_PRESENT") (class "Default")
      (node (ref "IC25") (pin "25") (pinfunction "GPA4_25") (pintype "bidirectional"))
      (node (ref "IC29") (pin "8") (pinfunction "P0_4_8") (pintype "bidirectional"))
    )
    (net (code "61") (name "/SFP_0.RATE_SELECT") (class "Default")
      (node (ref "IC25") (pin "24") (pinfunction "GPA3_24") (pintype "bidirectional"))
      (node (ref "IC29") (pin "7") (pinfunction "P0_3_7") (pintype "bidirectional"))
    )
    (net (code "62") (name "/SFP_0.RATE_SELECT1") (class "Default")
      (node (ref "IC25") (pin "23") (pinfunction "GPA2_23") (pintype "bidirectional"))
      (node (ref "IC29") (pin "6") (pinfunction "P0_2_6") (pintype "bidirectional"))
    )
    (net (code "63") (name "/SFP_0.SCL") (class "Default")
      (node (ref "IC15") (pin "2") (pinfunction "SC0_2") (pintype "bidirectional"))
      (node (ref "R184") (pin "1") (pinfunction "1_1") (pintype "passive"))
    )
    (net (code "64") (name "/SFP_0.SDA") (class "Default")
      (node (ref "IC15") (pin "1") (pinfunction "SD0_1") (pintype "bidirectional"))
      (node (ref "R183") (pin "1") (pinfunction "1_1") (pintype "passive"))
    )
    (net (code "65") (name "/SFP_0.TX_DISABLE") (class "Default")
      (node (ref "IC25") (pin "22") (pinfunction "GPA1_22") (pintype "bidirectional"))
      (node (ref "IC29") (pin "5") (pinfunction "P0_1_5") (pintype "bidirectional"))
    )
    (net (code "66") (name "/SFP_0.TX_FAULT") (class "Default")
      (node (ref "IC25") (pin "21") (pinfunction "GPA0_21") (pintype "bidirectional"))
      (node (ref "IC29") (pin "4") (pinfunction "P0_0_4") (pintype "bidirectional"))
    )
    (net (code "68") (name "/SFP_1.LED") (class "Default")
      (node (ref "IC25") (pin "7") (pinfunction "GPB6_7") (pintype "bidirectional"))
      (node (ref "IC29") (pin "19") (pinfunction "P1_6_19") (pintype "bidirectional"))
    )
    (net (code "69") (name "/SFP_1.LOS") (class "Default")
      (node (ref "IC25") (pin "6") (pinfunction "GPB5_6") (pintype "bidirectional"))
      (node (ref "IC29") (pin "18") (pinfunction "P1_5_18") (pintype "bidirectional"))
    )
    (net (code "70") (name "/SFP_1.MOD_PRESENT") (class "Default")
      (node (ref "IC25") (pin "5") (pinfunction "GPB4_5") (pintype "bidirectional"))
      (node (ref "IC29") (pin "17") (pinfunction "P1_4_17") (pintype "bidirectional"))
    )
    (net (code "71") (name "/SFP_1.RATE_SELECT") (class "Default")
      (node (ref "IC25") (pin "4") (pinfunction "GPB3_4") (pintype "bidirectional"))
      (node (ref "IC29") (pin "16") (pinfunction "P1_3_16") (pintype "bidirectional"))
    )
    (net (code "72") (name "/SFP_1.RATE_SELECT1") (class "Default")
      (node (ref "IC25") (pin "3") (pinfunction "GPB2_3") (pintype "bidirectional"))
      (node (ref "IC29") (pin "15") (pinfunction "P1_2_15") (pintype "bidirectional"))
    )
    (net (code "73") (name "/SFP_1.SCL") (class "Default")
      (node (ref "IC15") (pin "4") (pinfunction "SC1_4") (pintype "bidirectional"))
      (node (ref "R186") (pin "1") (pinfunction "1_1") (pintype "passive"))
    )
    (net (code "74") (name "/SFP_1.SDA") (class "Default")
      (node (ref "IC15") (pin "3") (pinfunction "SD1_3") (pintype "bidirectional"))
      (node (ref "R185") (pin "1") (pinfunction "1_1") (pintype "passive"))
    )
    (net (code "75") (name "/SFP_1.TX_DISABLE") (class "Default")
      (node (ref "IC25") (pin "2") (pinfunction "GPB1_2") (pintype "bidirectional"))
      (node (ref "IC29") (pin "14") (pinfunction "P1_1_14") (pintype "bidirectional"))
    )
    (net (code "76") (name "/SFP_1.TX_FAULT") (class "Default")
      (node (ref "IC25") (pin "1") (pinfunction "GPB0_1") (pintype "bidirectional"))
      (node (ref "IC29") (pin "13") (pinfunction "P1_0_13") (pintype "bidirectional"))
    )
    (net (code "78") (name "/SFP_2.A_RATE_SELECT") (class "Default")
      (node (ref "IC24") (pin "24") (pinfunction "GPA3_24") (pintype "bidirectional"))
      (node (ref "IC28") (pin "7") (pinfunction "P0_3_7") (pintype "bidirectional"))
      (node (ref "R82") (pin "1") (pinfunction "1_1") (pintype "passive"))
    )
    (net (code "79") (name "/SFP_2.LED") (class "Default")
      (node (ref "IC24") (pin "27") (pinfunction "GPA6_27") (pintype "bidirectional"))
      (node (ref "IC28") (pin "10") (pinfunction "P0_6_10") (pintype "bidirectional"))
    )
    (net (code "80") (name "/SFP_2.LOS") (class "Default")
      (node (ref "IC24") (pin "26") (pinfunction "GPA5_26") (pintype "bidirectional"))
      (node (ref "IC28") (pin "9") (pinfunction "P0_5_9") (pintype "bidirectional"))
    )
    (net (code "81") (name "/SFP_2.MOD_PRESENT") (class "Default")
      (node (ref "IC24") (pin "25") (pinfunction "GPA4_25") (pintype "bidirectional"))
      (node (ref "IC28") (pin "8") (pinfunction "P0_4_8") (pintype "bidirectional"))
    )
    (net (code "82") (name "/SFP_2.RATE_SELECT") (class "Default")
      (node (ref "R175") (pin "2") (pinfunction "2_2") (pintype "passive"))
      (node (ref "R82") (pin "2") (pinfunction "2_2") (pintype "passive"))
    )
    (net (code "83") (name "/SFP_2.RATE_SELECT1") (class "Default")
      (node (ref "IC24") (pin "23") (pinfunction "GPA2_23") (pintype "bidirectional"))
      (node (ref "IC28") (pin "6") (pinfunction "P0_2_6") (pintype "bidirectional"))
    )
    (net (code "84") (name "/SFP_2.SCL") (class "Default")
      (node (ref "IC15") (pin "6") (pinfunction "SC2_6") (pintype "bidirectional"))
      (node (ref "R188") (pin "1") (pinfunction "1_1") (pintype "passive"))
    )
    (net (code "85") (name "/SFP_2.SDA") (class "Default")
      (node (ref "IC15") (pin "5") (pinfunction "SD2_5") (pintype "bidirectional"))
      (node (ref "R187") (pin "1") (pinfunction "1_1") (pintype "passive"))
    )
    (net (code "86") (name "/SFP_2.TX_DISABLE") (class "Default")
      (node (ref "IC24") (pin "22") (pinfunction "GPA1_22") (pintype "bidirectional"))
      (node (ref "IC28") (pin "5") (pinfunction "P0_1_5") (pintype "bidirectional"))
    )
    (net (code "87") (name "/SFP_2.TX_FAULT") (class "Default")
      (node (ref "IC24") (pin "21") (pinfunction "GPA0_21") (pintype "bidirectional"))
      (node (ref "IC28") (pin "4") (pinfunction "P0_0_4") (pintype "bidirectional"))
    )
    (net (code "89") (name "/SFP_3.LED") (class "Default")
      (node (ref "IC24") (pin "7") (pinfunction "GPB6_7") (pintype "bidirectional"))
      (node (ref "IC28") (pin "19") (pinfunction "P1_6_19") (pintype "bidirectional"))
    )
    (net (code "90") (name "/SFP_3.LOS") (class "Default")
      (node (ref "IC24") (pin "6") (pinfunction "GPB5_6") (pintype "bidirectional"))
      (node (ref "IC28") (pin "18") (pinfunction "P1_5_18") (pintype "bidirectional"))
    )
    (net (code "91") (name "/SFP_3.MOD_PRESENT") (class "Default")
      (node (ref "IC24") (pin "5") (pinfunction "GPB4_5") (pintype "bidirectional"))
      (node (ref "IC28") (pin "17") (pinfunction "P1_4_17") (pintype "bidirectional"))
    )
    (net (code "92") (name "/SFP_3.RATE_SELECT") (class "Default")
      (node (ref "IC24") (pin "4") (pinfunction "GPB3_4") (pintype "bidirectional"))
      (node (ref "IC28") (pin "16") (pinfunction "P1_3_16") (pintype "bidirectional"))
    )
    (net (code "93") (name "/SFP_3.RATE_SELECT1") (class "Default")
      (node (ref "IC24") (pin "3") (pinfunction "GPB2_3") (pintype "bidirectional"))
      (node (ref "IC28") (pin "15") (pinfunction "P1_2_15") (pintype "bidirectional"))
    )
    (net (code "94") (name "/SFP_3.SCL") (class "Default")
      (node (ref "IC15") (pin "11") (pinfunction "SC4_11") (pintype "bidirectional"))
      (node (ref "R177") (pin "1") (pinfunction "1_1") (pintype "passive"))
    )
    (net (code "95") (name "/SFP_3.SDA") (class "Default")
      (node (ref "IC15") (pin "10") (pinfunction "SD4_10") (pintype "bidirectional"))
      (node (ref "R176") (pin "1") (pinfunction "1_1") (pintype "passive"))
    )
    (net (code "96") (name "/SFP_3.TX_DISABLE") (class "Default")
      (node (ref "IC24") (pin "2") (pinfunction "GPB1_2") (pintype "bidirectional"))
      (node (ref "IC28") (pin "14") (pinfunction "P1_1_14") (pintype "bidirectional"))
    )
    (net (code "97") (name "/SFP_3.TX_FAULT") (class "Default")
      (node (ref "IC24") (pin "1") (pinfunction "GPB0_1") (pintype "bidirectional"))
      (node (ref "IC28") (pin "13") (pinfunction "P1_0_13") (pintype "bidirectional"))
    )
    (net (code "99") (name "/SHARED_SCL") (class "Default")
      (node (ref "IC15") (pin "8") (pinfunction "SC3_8") (pintype "bidirectional"))
      (node (ref "IC24") (pin "12") (pinfunction "SCL_12") (pintype "input"))
      (node (ref "IC25") (pin "12") (pinfunction "SCL_12") (pintype "input"))
      (node (ref "IC28") (pin "22") (pinfunction "SCL_22") (pintype "input"))
      (node (ref "IC29") (pin "22") (pinfunction "SCL_22") (pintype "input"))
      (node (ref "IC34") (pin "12") (pinfunction "SCL_12") (pintype "input"))
      (node (ref "IC38") (pin "22") (pinfunction "SCL_22") (pintype "input"))
      (node (ref "R190") (pin "1") (pinfunction "1_1") (pintype "passive"))
      (node (ref "TP3") (pin "1") (pinfunction "1_1") (pintype "bidirectional"))
    )
    (net (code "100") (name "/SHARED_SDA") (class "Default")
      (node (ref "IC15") (pin "7") (pinfunction "SD3_7") (pintype "bidirectional"))
      (node (ref "IC24") (pin "13") (pinfunction "SDA_13") (pintype "bidirectional"))
      (node (ref "IC25") (pin "13") (pinfunction "SDA_13") (pintype "bidirectional"))
      (node (ref "IC28") (pin "23") (pinfunction "SDA_23") (pintype "bidirectional"))
      (node (ref "IC29") (pin "23") (pinfunction "SDA_23") (pintype "bidirectional"))
      (node (ref "IC34") (pin "13") (pinfunction "SDA_13") (pintype "bidirectional"))
      (node (ref "IC38") (pin "23") (pinfunction "SDA_23") (pintype "bidirectional"))
      (node (ref "R189") (pin "1") (pinfunction "1_1") (pintype "passive"))
      (node (ref "TP2") (pin "1") (pinfunction "1_1") (pintype "bidirectional"))
    )
    (net (code "101") (name "/VUSB_PRESENT_N") (class "Default")
      (node (ref "IC25") (pin "28") (pinfunction "GPA7_28") (pintype "bidirectional"))
      (node (ref "IC29") (pin "11") (pinfunction "P0_7_11") (pintype "bidirectional"))
    )
    (net (code "106") (name "/~{OE}") (class "Default")
      (node (ref "IC27") (pin "19") (pinfunction "~{OE}_19") (pintype "input"))
      (node (ref "R147") (pin "2") (pinfunction "2_2") (pintype "passive"))
    )
    (net (code "107") (name "/~{OE}b") (class "Default")
      (node (ref "IC34") (pin "8") (pinfunction "GPB7_8") (pintype "bidirectional"))
      (node (ref "IC38") (pin "20") (pinfunction "P1_7_20") (pintype "bidirectional"))
      (node (ref "R147") (pin "1") (pinfunction "1_1") (pintype "passive"))
    )
    (net (code "108") (name "GND") (class "Default")
      (node (ref "C186") (pin "1") (pinfunction "1_1") (pintype "passive"))
      (node (ref "C192") (pin "1") (pinfunction "1_1") (pintype "passive"))
      (node (ref "C193") (pin "1") (pinfunction "1_1") (pintype "passive"))
      (node (ref "C197") (pin "1") (pinfunction "1_1") (pintype "passive"))
      (node (ref "C198") (pin "1") (pinfunction "1_1") (pintype "passive"))
      (node (ref "C227") (pin "1") (pinfunction "1_1") (pintype "passive"))
      (node (ref "C292") (pin "1") (pinfunction "1_1") (pintype "passive"))
      (node (ref "C305") (pin "1") (pinfunction "1_1") (pintype "passive"))
      (node (ref "C306") (pin "1") (pinfunction "1_1") (pintype "passive"))
      (node (ref "C307") (pin "1") (pinfunction "1_1") (pintype "passive"))
      (node (ref "C427") (pin "1") (pinfunction "1_1") (pintype "passive"))
      (node (ref "IC15") (pin "18") (pinfunction "A2_18") (pintype "input"))
      (node (ref "IC15") (pin "22") (pinfunction "A0_22") (pintype "input"))
      (node (ref "IC15") (pin "23") (pinfunction "A1_23") (pintype "input"))
      (node (ref "IC15") (pin "25") (pinfunction "EP_25") (pintype "power_in"))
      (node (ref "IC15") (pin "9") (pinfunction "GND_9") (pintype "power_in"))
      (node (ref "IC24") (pin "10") (pinfunction "VSS_10") (pintype "power_in"))
      (node (ref "IC24") (pin "16") (pinfunction "A1_16") (pintype "input"))
      (node (ref "IC24") (pin "17") (pinfunction "A2_17") (pintype "input"))
      (node (ref "IC25") (pin "10") (pinfunction "VSS_10") (pintype "power_in"))
      (node (ref "IC25") (pin "15") (pinfunction "A0_15") (pintype "input"))
      (node (ref "IC25") (pin "16") (pinfunction "A1_16") (pintype "input"))
      (node (ref "IC25") (pin "17") (pinfunction "A2_17") (pintype "input"))
      (node (ref "IC27") (pin "10") (pinfunction "GND_10") (pintype "power_in"))
      (node (ref "IC28") (pin "12") (pinfunction "GND_12") (pintype "power_in"))
      (node (ref "IC28") (pin "2") (pinfunction "A1_2") (pintype "input"))
      (node (ref "IC29") (pin "12") (pinfunction "GND_12") (pintype "power_in"))
      (node (ref "IC29") (pin "2") (pinfunction "A1_2") (pintype "input"))
      (node (ref "IC29") (pin "21") (pinfunction "A0_21") (pintype "input"))
      (node (ref "IC30") (pin "2") (pinfunction "VSS_2") (pintype "power_in"))
      (node (ref "IC30") (pin "4") (pinfunction "A1_4") (pintype "input"))
      (node (ref "IC30") (pin "5") (pinfunction "A0_5") (pintype "input"))
      (node (ref "IC31") (pin "1") (pinfunction "A0_1") (pintype "input"))
      (node (ref "IC31") (pin "2") (pinfunction "A1_2") (pintype "input"))
      (node (ref "IC31") (pin "3") (pinfunction "A2_3") (pintype "input"))
      (node (ref "IC31") (pin "4") (pinfunction "VSS_4") (pintype "power_in"))
      (node (ref "IC34") (pin "10") (pinfunction "VSS_10") (pintype "power_in"))
      (node (ref "IC34") (pin "15") (pinfunction "A0_15") (pintype "input"))
      (node (ref "IC34") (pin "17") (pinfunction "A2_17") (pintype "input"))
      (node (ref "IC35") (pin "10") (pinfunction "GND_10") (pintype "power_in"))
      (node (ref "IC35") (pin "19") (pinfunction "~{OE}_19") (pintype "input"))
      (node (ref "IC38") (pin "12") (pinfunction "GND_12") (pintype "power_in"))
      (node (ref "IC38") (pin "21") (pinfunction "A0_21") (pintype "input"))
      (node (ref "R33") (pin "1") (pinfunction "1_1") (pintype "passive"))
      (node (ref "R46") (pin "1") (pinfunction "1_1") (pintype "passive"))
      (node (ref "T21") (pin "2") (pinfunction "S_2") (pintype "passive"))
      (node (ref "T22") (pin "2") (pinfunction "S_2") (pintype "passive"))
    )
    (net (code "109") (name "P3V3") (class "Default")
      (node (ref "C186") (pin "2") (pinfunction "2_2") (pintype "passive"))
      (node (ref "C192") (pin "2") (pinfunction "2_2") (pintype "passive"))
      (node (ref "C193") (pin "2") (pinfunction "2_2") (pintype "passive"))
      (node (ref "C197") (pin "2") (pinfunction "2_2") (pintype "passive"))
      (node (ref "C198") (pin "2") (pinfunction "2_2") (pintype "passive"))
      (node (ref "C227") (pin "2") (pinfunction "2_2") (pintype "passive"))
      (node (ref "C292") (pin "2") (pinfunction "2_2") (pintype "passive"))
      (node (ref "C305") (pin "2") (pinfunction "2_2") (pintype "passive"))
      (node (ref "C306") (pin "2") (pinfunction "2_2") (pintype "passive"))
      (node (ref "C307") (pin "2") (pinfunction "2_2") (pintype "passive"))
      (node (ref "C427") (pin "2") (pinfunction "2_2") (pintype "passive"))
      (node (ref "IC15") (pin "21") (pinfunction "VCC_21") (pintype "power_in"))
      (node (ref "IC24") (pin "15") (pinfunction "A0_15") (pintype "input"))
      (node (ref "IC24") (pin "9") (pinfunction "VDD_9") (pintype "power_in"))
      (node (ref "IC25") (pin "9") (pinfunction "VDD_9") (pintype "power_in"))
      (node (ref "IC27") (pin "20") (pinfunction "VCC_20") (pintype "power_in"))
      (node (ref "IC28") (pin "21") (pinfunction "A0_21") (pintype "input"))
      (node (ref "IC28") (pin "24") (pinfunction "VCC_24") (pintype "power_in"))
      (node (ref "IC29") (pin "24") (pinfunction "VCC_24") (pintype "power_in"))
      (node (ref "IC30") (pin "6") (pinfunction "VCC_6") (pintype "power_in"))
      (node (ref "IC31") (pin "8") (pinfunction "VCC_8") (pintype "power_in"))
      (node (ref "IC34") (pin "16") (pinfunction "A1_16") (pintype "input"))
      (node (ref "IC34") (pin "18") (pinfunction "~{RESET}_18") (pintype "input"))
      (node (ref "IC34") (pin "9") (pinfunction "VDD_9") (pintype "power_in"))
      (node (ref "IC35") (pin "1") (pinfunction "DIR_1") (pintype "input"))
      (node (ref "IC35") (pin "20") (pinfunction "VCC_20") (pintype "power_in"))
      (node (ref "IC38") (pin "2") (pinfunction "A1_2") (pintype "input"))
      (node (ref "IC38") (pin "24") (pinfunction "VCC_24") (pintype "power_in"))
      (node (ref "IC38") (pin "3") (pinfunction "~{RESET}_3") (pintype "input"))
      (node (ref "R131") (pin "1") (pinfunction "1_1") (pintype "passive"))
      (node (ref "R132") (pin "1") (pinfunction "1_1") (pintype "passive"))
      (node (ref "R148") (pin "2") (pinfunction "2_2") (pintype "passive"))
      (node (ref "R149") (pin "2") (pinfunction "2_2") (pintype "passive"))
      (node (ref "R151") (pin "2") (pinfunction "2_2") (pintype "passive"))
      (node (ref "R176") (pin "2") (pinfunction "2_2") (pintype "passive"))
      (node (ref "R177") (pin "2") (pinfunction "2_2") (pintype "passive"))
      (node (ref "R178") (pin "2") (pinfunction "2_2") (pintype "passive"))
      (node (ref "R179") (pin "2") (pinfunction "2_2") (pintype "passive"))
      (node (ref "R180") (pin "2") (pinfunction "2_2") (pintype "passive"))
      (node (ref "R181") (pin "2") (pinfunction "2_2") (pintype "passive"))
      (node (ref "R182") (pin "2") (pinfunction "2_2") (pintype "passive"))
      (node (ref "R183") (pin "2") (pinfunction "2_2") (pintype "passive"))
      (node (ref "R184") (pin "2") (pinfunction "2_2") (pintype "passive"))
      (node (ref "R185") (pin "2") (pinfunction "2_2") (pintype "passive"))
      (node (ref "R186") (pin "2") (pinfunction "2_2") (pintype "passive"))
      (node (ref "R187") (pin "2") (pinfunction "2_2") (pintype "passive"))
      (node (ref "R188") (pin "2") (pinfunction "2_2") (pintype "passive"))
      (node (ref "R189") (pin "2") (pinfunction "2_2") (pintype "passive"))
      (node (ref "R190") (pin "2") (pinfunction "2_2") (pintype "passive"))
      (node (ref "R191") (pin "2") (pinfunction "2_2") (pintype "passive"))
      (node (ref "R192") (pin "2") (pinfunction "2_2") (pintype "passive"))
      (node (ref "R212") (pin "2") (pinfunction "2_2") (pintype "passive"))
      (node (ref "R225") (pin "2") (pinfunction "2_2") (pintype "passive"))
      (node (ref "R264") (pin "2") (pinfunction "2_2") (pintype "passive"))
      (node (ref "R265") (pin "2") (pinfunction "2_2") (pintype "passive"))
      (node (ref "R66") (pin "2") (pinfunction "2_2") (pintype "passive"))
    )
    (net (code "110") (name "unconnected-(IC24-INTB-Pad19)") (class "Default")
      (node (ref "IC24") (pin "19") (pinfunction "INTB_19") (pintype "output+no_connect"))
    )
    (net (code "111") (name "unconnected-(IC24-NC-Pad11)") (class "Default")
      (node (ref "IC24") (pin "11") (pinfunction "NC_11") (pintype "passive+no_connect"))
    )
    (net (code "112") (name "unconnected-(IC24-NC-Pad14)") (class "Default")
      (node (ref "IC24") (pin "14") (pinfunction "NC_14") (pintype "passive+no_connect"))
    )
    (net (code "113") (name "unconnected-(IC25-INTB-Pad19)") (class "Default")
      (node (ref "IC25") (pin "19") (pinfunction "INTB_19") (pintype "output+no_connect"))
    )
    (net (code "114") (name "unconnected-(IC25-NC-Pad11)") (class "Default")
      (node (ref "IC25") (pin "11") (pinfunction "NC_11") (pintype "passive+no_connect"))
    )
    (net (code "115") (name "unconnected-(IC25-NC-Pad14)") (class "Default")
      (node (ref "IC25") (pin "14") (pinfunction "NC_14") (pintype "passive+no_connect"))
    )
    (net (code "116") (name "unconnected-(IC31-NC-Pad7)") (class "Default")
      (node (ref "IC31") (pin "7") (pinfunction "NC_7") (pintype "passive+no_connect"))
    )
    (net (code "117") (name "unconnected-(IC34-GPB0-Pad1)") (class "Default")
      (node (ref "IC34") (pin "1") (pinfunction "GPB0_1") (pintype "bidirectional+no_connect"))
    )
    (net (code "118") (name "unconnected-(IC34-GPB1-Pad2)") (class "Default")
      (node (ref "IC34") (pin "2") (pinfunction "GPB1_2") (pintype "bidirectional+no_connect"))
    )
    (net (code "119") (name "unconnected-(IC34-GPB2-Pad3)") (class "Default")
      (node (ref "IC34") (pin "3") (pinfunction "GPB2_3") (pintype "bidirectional+no_connect"))
    )
    (net (code "120") (name "unconnected-(IC34-GPB3-Pad4)") (class "Default")
      (node (ref "IC34") (pin "4") (pinfunction "GPB3_4") (pintype "bidirectional+no_connect"))
    )
    (net (code "121") (name "unconnected-(IC34-GPB4-Pad5)") (class "Default")
      (node (ref "IC34") (pin "5") (pinfunction "GPB4_5") (pintype "bidirectional+no_connect"))
    )
    (net (code "122") (name "unconnected-(IC34-INTA-Pad20)") (class "Default")
      (node (ref "IC34") (pin "20") (pinfunction "INTA_20") (pintype "output+no_connect"))
    )
    (net (code "123") (name "unconnected-(IC34-INTB-Pad19)") (class "Default")
      (node (ref "IC34") (pin "19") (pinfunction "INTB_19") (pintype "output+no_connect"))
    )
    (net (code "124") (name "unconnected-(IC34-NC-Pad11)") (class "Default")
      (node (ref "IC34") (pin "11") (pinfunction "NC_11") (pintype "passive+no_connect"))
    )
    (net (code "125") (name "unconnected-(IC34-NC-Pad14)") (class "Default")
      (node (ref "IC34") (pin "14") (pinfunction "NC_14") (pintype "passive+no_connect"))
    )
    (net (code "126") (name "unconnected-(IC38-P1_0-Pad13)") (class "Default")
      (node (ref "IC38") (pin "13") (pinfunction "P1_0_13") (pintype "bidirectional+no_connect"))
    )
    (net (code "127") (name "unconnected-(IC38-P1_1-Pad14)") (class "Default")
      (node (ref "IC38") (pin "14") (pinfunction "P1_1_14") (pintype "bidirectional+no_connect"))
    )
    (net (code "128") (name "unconnected-(IC38-P1_2-Pad15)") (class "Default")
      (node (ref "IC38") (pin "15") (pinfunction "P1_2_15") (pintype "bidirectional+no_connect"))
    )
    (net (code "129") (name "unconnected-(IC38-P1_3-Pad16)") (class "Default")
      (node (ref "IC38") (pin "16") (pinfunction "P1_3_16") (pintype "bidirectional+no_connect"))
    )
    (net (code "130") (name "unconnected-(IC38-P1_4-Pad17)") (class "Default")
      (node (ref "IC38") (pin "17") (pinfunction "P1_4_17") (pintype "bidirectional+no_connect"))
    )
    (net (code "131") (name "unconnected-(IC38-~{INT}-Pad1)") (class "Default")
      (node (ref "IC38") (pin "1") (pinfunction "~{INT}_1") (pintype "open_collector+no_connect"))
    )
  )
)
